# opamp_amplifier.net
KiCad netlist of a schematic drawn in EAGLE
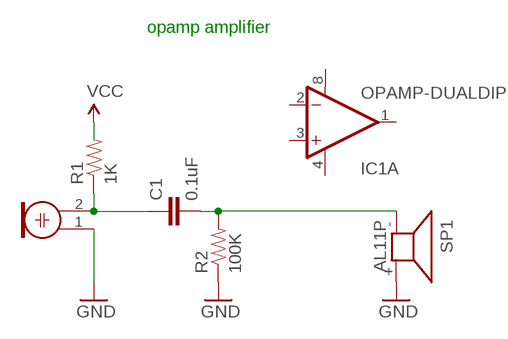
[diagram p0: schematic, sheet 1]

(export (version "E")
  (design (tool "Eeschema 10.0.6"))
  (components
    (comp (ref "C1")
      (value "0.1uF")
      (footprint "eagle-import:CAP-PTH-SMALL2")
      (libsource (lib "eagle-import") (part "CAPPTH2"))
    )
    (comp (ref "IC1")
      (value "OPAMP-DUALDIP")
      (footprint "eagle-import:DIP08")
      (libsource (lib "eagle-import") (part "OPAMP-DUALDIP"))
    )
    (comp (ref "M1")
      (value "ELECTRET_MICROPHON-F6050AP")
      (footprint "eagle-import:F6050AP")
      (libsource (lib "eagle-import") (part "ELECTRET_MICROPHON-F6050AP"))
    )
    (comp (ref "R1")
      (value "1K")
      (footprint "eagle-import:AXIAL-0.3")
      (libsource (lib "eagle-import") (part "RESISTORAXIAL-0.3"))
    )
    (comp (ref "R2")
      (value "100K")
      (footprint "eagle-import:AXIAL-0.3")
      (libsource (lib "eagle-import") (part "RESISTORAXIAL-0.3"))
    )
    (comp (ref "SP1")
      (value "AL11P")
      (footprint "eagle-import:AL11P")
      (libsource (lib "eagle-import") (part "AL11P"))
    )
  )
  (nets
    (net (code "1") (name "/V+") (class "Default")
      (node (ref "IC1") (pin "8") (pinfunction "V+_8") (pintype "power_in"))
    )
    (net (code "2") (name "/V-") (class "Default")
      (node (ref "IC1") (pin "4") (pinfunction "V-_4") (pintype "power_in"))
    )
    (net (code "3") (name "GND") (class "Default")
      (node (ref "M1") (pin "1") (pinfunction "1_1") (pintype "passive"))
      (node (ref "R2") (pin "P$1") (pinfunction "1_P$1") (pintype "passive"))
      (node (ref "SP1") (pin "+") (pinfunction "2_+") (pintype "passive"))
    )
    (net (code "4") (name "Net-(R1-1)") (class "Default")
      (node (ref "C1") (pin "1") (pinfunction "1_1") (pintype "passive"))
      (node (ref "M1") (pin "2") (pinfunction "2_2") (pintype "passive"))
      (node (ref "R1") (pin "P$1") (pinfunction "1_P$1") (pintype "passive"))
    )
    (net (code "5") (name "Net-(R2-2)") (class "Default")
      (node (ref "C1") (pin "2") (pinfunction "2_2") (pintype "passive"))
      (node (ref "R2") (pin "P$2") (pinfunction "2_P$2") (pintype "passive"))
      (node (ref "SP1") (pin "-") (pinfunction "1_-") (pintype "passive"))
    )
    (net (code "6") (name "VCC") (class "Default")
      (node (ref "R1") (pin "P$2") (pinfunction "2_P$2") (pintype "passive"))
    )
    (net (code "7") (name "unconnected-(IC1A-+IN-Pad3)") (class "Default")
      (node (ref "IC1") (pin "3") (pinfunction "+IN_3") (pintype "input"))
    )
    (net (code "8") (name "unconnected-(IC1A--IN-Pad2)") (class "Default")
      (node (ref "IC1") (pin "2") (pinfunction "-IN_2") (pintype "input"))
    )
    (net (code "9") (name "unconnected-(IC1A-OUT-Pad1)") (class "Default")
      (node (ref "IC1") (pin "1") (pinfunction "OUT_1") (pintype "output"))
    )
  )
)
